# ampelsteuerungeagle.net
KiCad netlist of a schematic drawn in EAGLE
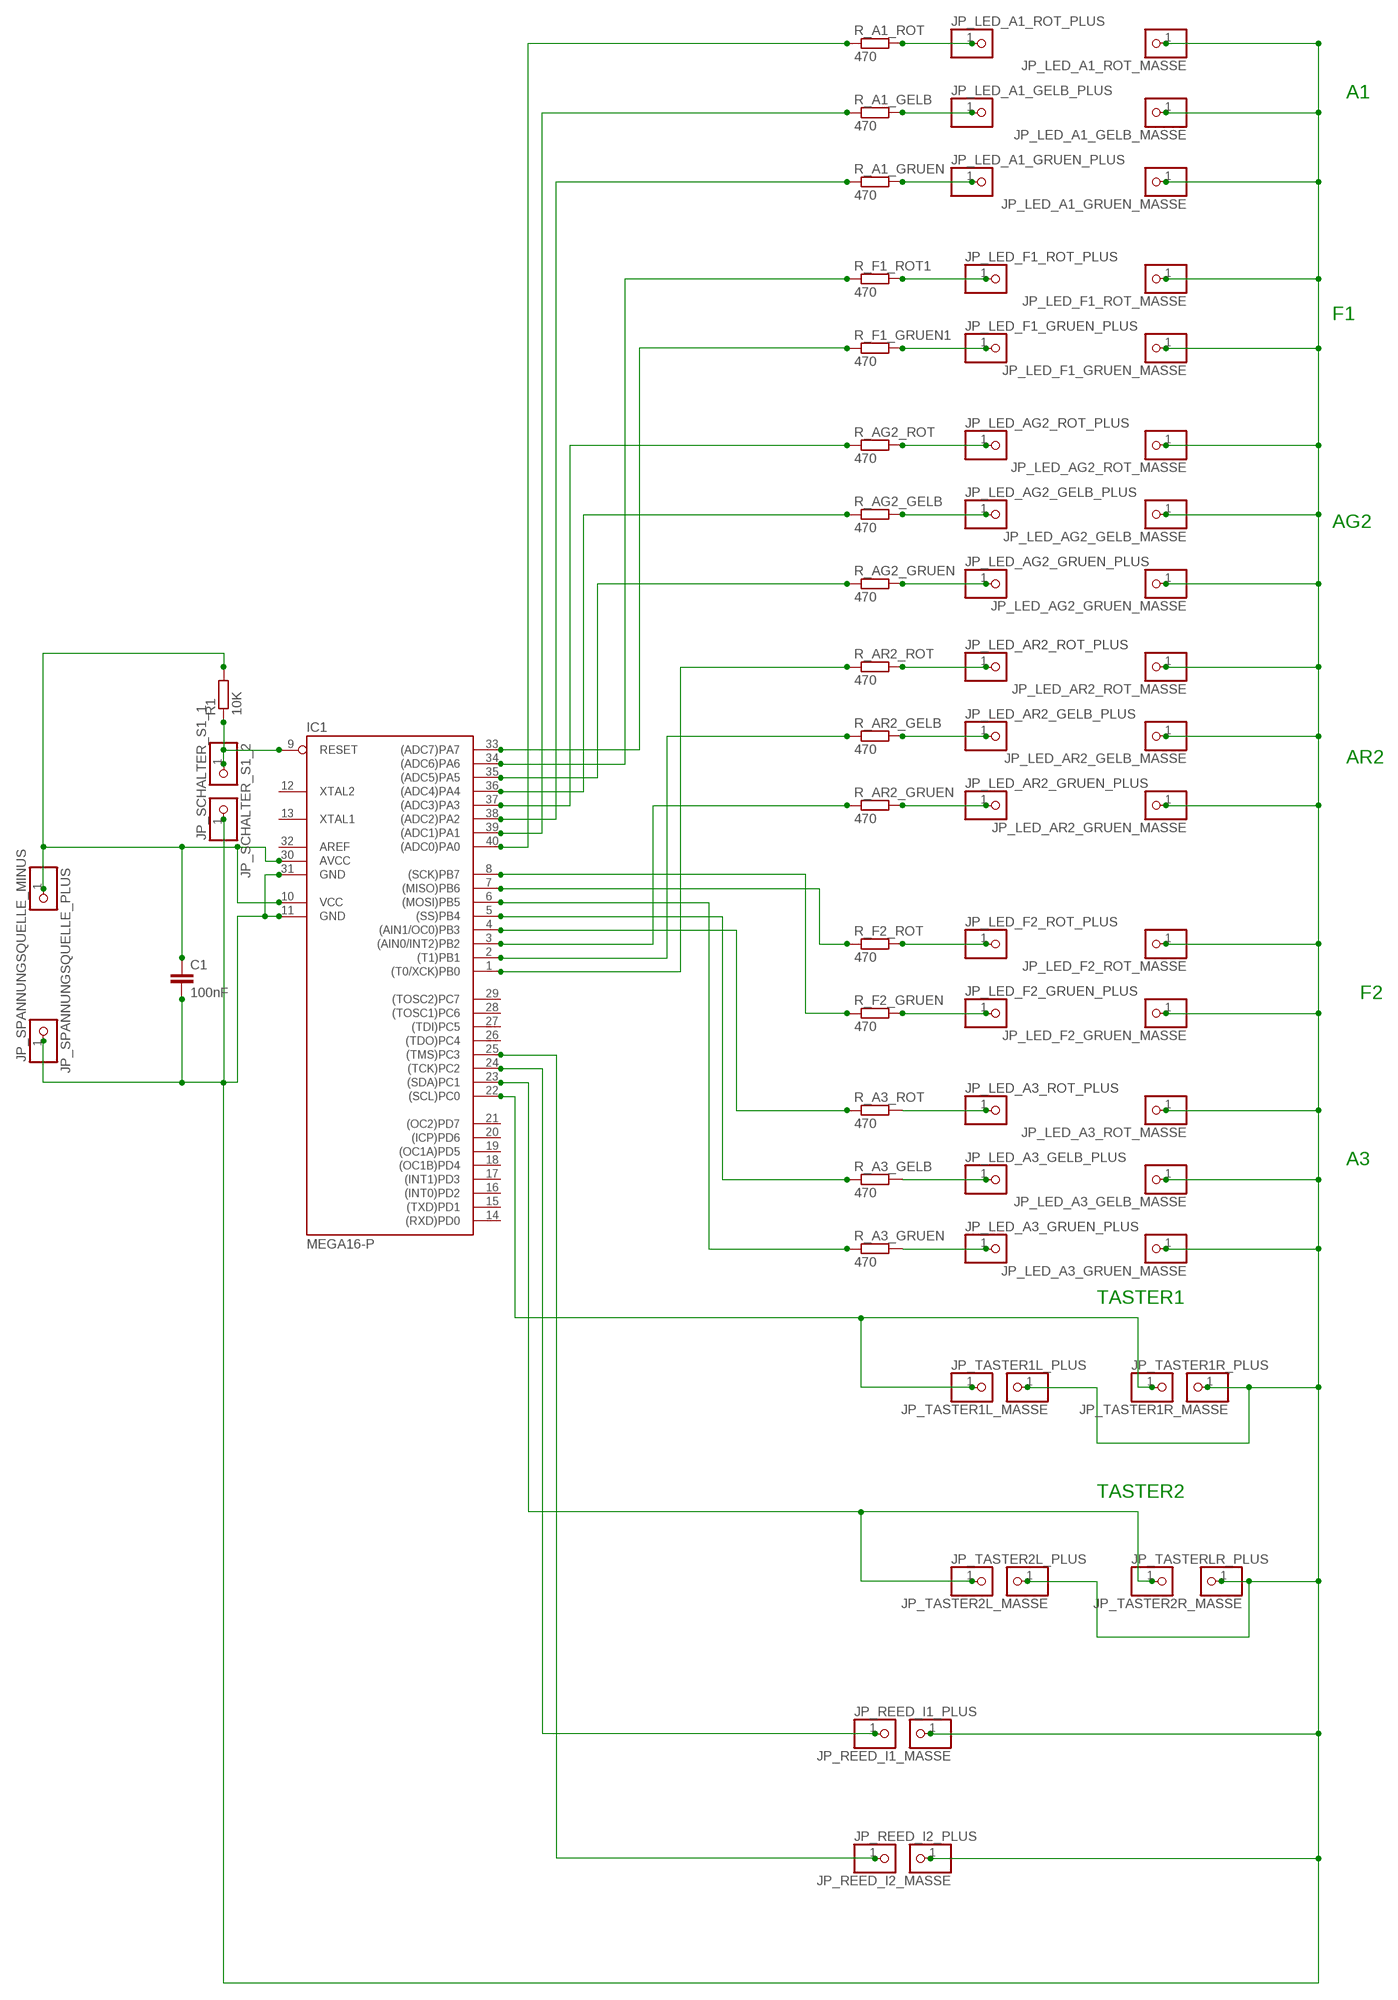
[diagram p0: schematic, sheet 1]

(export (version "E")
  (design (tool "Eeschema 10.0.6"))
  (components
    (comp (ref "C1")
      (value "100nF")
      (footprint "eagle-import:C025-024X044")
      (libsource (lib "eagle-import") (part "C-EU025-024X044"))
    )
    (comp (ref "IC1")
      (value "MEGA16-P")
      (footprint "eagle-import:DIL40")
      (fields (field (name "MPN") "ATMEGA16-16PU"))
      (libsource (lib "eagle-import") (part "MEGA16-P"))
    )
    (comp (ref "JP_LED_A1_GELB_MASSE")
      (value "PINHD-1X1")
      (footprint "eagle-import:1X01")
      (libsource (lib "eagle-import") (part "PINHD-1X1"))
    )
    (comp (ref "JP_LED_A1_GELB_PLUS")
      (value "PINHD-1X1")
      (footprint "eagle-import:1X01")
      (libsource (lib "eagle-import") (part "PINHD-1X1"))
    )
    (comp (ref "JP_LED_A1_GRUEN_MASSE")
      (value "PINHD-1X1")
      (footprint "eagle-import:1X01")
      (libsource (lib "eagle-import") (part "PINHD-1X1"))
    )
    (comp (ref "JP_LED_A1_GRUEN_PLUS")
      (value "PINHD-1X1")
      (footprint "eagle-import:1X01")
      (libsource (lib "eagle-import") (part "PINHD-1X1"))
    )
    (comp (ref "JP_LED_A1_ROT_MASSE")
      (value "PINHD-1X1")
      (footprint "eagle-import:1X01")
      (libsource (lib "eagle-import") (part "PINHD-1X1"))
    )
    (comp (ref "JP_LED_A1_ROT_PLUS")
      (value "PINHD-1X1")
      (footprint "eagle-import:1X01")
      (libsource (lib "eagle-import") (part "PINHD-1X1"))
    )
    (comp (ref "JP_LED_A3_GELB_MASSE")
      (value "PINHD-1X1")
      (footprint "eagle-import:1X01")
      (libsource (lib "eagle-import") (part "PINHD-1X1"))
    )
    (comp (ref "JP_LED_A3_GELB_PLUS")
      (value "PINHD-1X1")
      (footprint "eagle-import:1X01")
      (libsource (lib "eagle-import") (part "PINHD-1X1"))
    )
    (comp (ref "JP_LED_A3_GRUEN_MASSE")
      (value "PINHD-1X1")
      (footprint "eagle-import:1X01")
      (libsource (lib "eagle-import") (part "PINHD-1X1"))
    )
    (comp (ref "JP_LED_A3_GRUEN_PLUS")
      (value "PINHD-1X1")
      (footprint "eagle-import:1X01")
      (libsource (lib "eagle-import") (part "PINHD-1X1"))
    )
    (comp (ref "JP_LED_A3_ROT_MASSE")
      (value "PINHD-1X1")
      (footprint "eagle-import:1X01")
      (libsource (lib "eagle-import") (part "PINHD-1X1"))
    )
    (comp (ref "JP_LED_A3_ROT_PLUS")
      (value "PINHD-1X1")
      (footprint "eagle-import:1X01")
      (libsource (lib "eagle-import") (part "PINHD-1X1"))
    )
    (comp (ref "JP_LED_AG2_GELB_MASSE")
      (value "PINHD-1X1")
      (footprint "eagle-import:1X01")
      (libsource (lib "eagle-import") (part "PINHD-1X1"))
    )
    (comp (ref "JP_LED_AG2_GELB_PLUS")
      (value "PINHD-1X1")
      (footprint "eagle-import:1X01")
      (libsource (lib "eagle-import") (part "PINHD-1X1"))
    )
    (comp (ref "JP_LED_AG2_GRUEN_MASSE")
      (value "PINHD-1X1")
      (footprint "eagle-import:1X01")
      (libsource (lib "eagle-import") (part "PINHD-1X1"))
    )
    (comp (ref "JP_LED_AG2_GRUEN_PLUS")
      (value "PINHD-1X1")
      (footprint "eagle-import:1X01")
      (libsource (lib "eagle-import") (part "PINHD-1X1"))
    )
    (comp (ref "JP_LED_AG2_ROT_MASSE")
      (value "PINHD-1X1")
      (footprint "eagle-import:1X01")
      (libsource (lib "eagle-import") (part "PINHD-1X1"))
    )
    (comp (ref "JP_LED_AG2_ROT_PLUS")
      (value "PINHD-1X1")
      (footprint "eagle-import:1X01")
      (libsource (lib "eagle-import") (part "PINHD-1X1"))
    )
    (comp (ref "JP_LED_AR2_GELB_MASSE")
      (value "PINHD-1X1")
      (footprint "eagle-import:1X01")
      (libsource (lib "eagle-import") (part "PINHD-1X1"))
    )
    (comp (ref "JP_LED_AR2_GELB_PLUS")
      (value "PINHD-1X1")
      (footprint "eagle-import:1X01")
      (libsource (lib "eagle-import") (part "PINHD-1X1"))
    )
    (comp (ref "JP_LED_AR2_GRUEN_MASSE")
      (value "PINHD-1X1")
      (footprint "eagle-import:1X01")
      (libsource (lib "eagle-import") (part "PINHD-1X1"))
    )
    (comp (ref "JP_LED_AR2_GRUEN_PLUS")
      (value "PINHD-1X1")
      (footprint "eagle-import:1X01")
      (libsource (lib "eagle-import") (part "PINHD-1X1"))
    )
    (comp (ref "JP_LED_AR2_ROT_MASSE")
      (value "PINHD-1X1")
      (footprint "eagle-import:1X01")
      (libsource (lib "eagle-import") (part "PINHD-1X1"))
    )
    (comp (ref "JP_LED_AR2_ROT_PLUS")
      (value "PINHD-1X1")
      (footprint "eagle-import:1X01")
      (libsource (lib "eagle-import") (part "PINHD-1X1"))
    )
    (comp (ref "JP_LED_F1_GRUEN_MASSE")
      (value "PINHD-1X1")
      (footprint "eagle-import:1X01")
      (libsource (lib "eagle-import") (part "PINHD-1X1"))
    )
    (comp (ref "JP_LED_F1_GRUEN_PLUS")
      (value "PINHD-1X1")
      (footprint "eagle-import:1X01")
      (libsource (lib "eagle-import") (part "PINHD-1X1"))
    )
    (comp (ref "JP_LED_F1_ROT_MASSE")
      (value "PINHD-1X1")
      (footprint "eagle-import:1X01")
      (libsource (lib "eagle-import") (part "PINHD-1X1"))
    )
    (comp (ref "JP_LED_F1_ROT_PLUS")
      (value "PINHD-1X1")
      (footprint "eagle-import:1X01")
      (libsource (lib "eagle-import") (part "PINHD-1X1"))
    )
    (comp (ref "JP_LED_F2_GRUEN_MASSE")
      (value "PINHD-1X1")
      (footprint "eagle-import:1X01")
      (libsource (lib "eagle-import") (part "PINHD-1X1"))
    )
    (comp (ref "JP_LED_F2_GRUEN_PLUS")
      (value "PINHD-1X1")
      (footprint "eagle-import:1X01")
      (libsource (lib "eagle-import") (part "PINHD-1X1"))
    )
    (comp (ref "JP_LED_F2_ROT_MASSE")
      (value "PINHD-1X1")
      (footprint "eagle-import:1X01")
      (libsource (lib "eagle-import") (part "PINHD-1X1"))
    )
    (comp (ref "JP_LED_F2_ROT_PLUS")
      (value "PINHD-1X1")
      (footprint "eagle-import:1X01")
      (libsource (lib "eagle-import") (part "PINHD-1X1"))
    )
    (comp (ref "JP_REED_I1_MASSE")
      (value "PINHD-1X1")
      (footprint "eagle-import:1X01")
      (libsource (lib "eagle-import") (part "PINHD-1X1"))
    )
    (comp (ref "JP_REED_I1_PLUS")
      (value "PINHD-1X1")
      (footprint "eagle-import:1X01")
      (libsource (lib "eagle-import") (part "PINHD-1X1"))
    )
    (comp (ref "JP_REED_I2_MASSE")
      (value "PINHD-1X1")
      (footprint "eagle-import:1X01")
      (libsource (lib "eagle-import") (part "PINHD-1X1"))
    )
    (comp (ref "JP_REED_I2_PLUS")
      (value "PINHD-1X1")
      (footprint "eagle-import:1X01")
      (libsource (lib "eagle-import") (part "PINHD-1X1"))
    )
    (comp (ref "JP_SCHALTER_S1_1")
      (value "PINHD-1X1")
      (footprint "eagle-import:1X01")
      (libsource (lib "eagle-import") (part "PINHD-1X1"))
    )
    (comp (ref "JP_SCHALTER_S1_2")
      (value "PINHD-1X1")
      (footprint "eagle-import:1X01")
      (libsource (lib "eagle-import") (part "PINHD-1X1"))
    )
    (comp (ref "JP_SPANNUNGSQUELLE_MINUS")
      (value "PINHD-1X1")
      (footprint "eagle-import:1X01")
      (libsource (lib "eagle-import") (part "PINHD-1X1"))
    )
    (comp (ref "JP_SPANNUNGSQUELLE_PLUS")
      (value "PINHD-1X1")
      (footprint "eagle-import:1X01")
      (libsource (lib "eagle-import") (part "PINHD-1X1"))
    )
    (comp (ref "JP_TASTER1L_MASSE")
      (value "PINHD-1X1")
      (footprint "eagle-import:1X01")
      (libsource (lib "eagle-import") (part "PINHD-1X1"))
    )
    (comp (ref "JP_TASTER1L_PLUS")
      (value "PINHD-1X1")
      (footprint "eagle-import:1X01")
      (libsource (lib "eagle-import") (part "PINHD-1X1"))
    )
    (comp (ref "JP_TASTER1R_MASSE")
      (value "PINHD-1X1")
      (footprint "eagle-import:1X01")
      (libsource (lib "eagle-import") (part "PINHD-1X1"))
    )
    (comp (ref "JP_TASTER1R_PLUS")
      (value "PINHD-1X1")
      (footprint "eagle-import:1X01")
      (libsource (lib "eagle-import") (part "PINHD-1X1"))
    )
    (comp (ref "JP_TASTER2L_MASSE")
      (value "PINHD-1X1")
      (footprint "eagle-import:1X01")
      (libsource (lib "eagle-import") (part "PINHD-1X1"))
    )
    (comp (ref "JP_TASTER2L_PLUS")
      (value "PINHD-1X1")
      (footprint "eagle-import:1X01")
      (libsource (lib "eagle-import") (part "PINHD-1X1"))
    )
    (comp (ref "JP_TASTER2R_MASSE")
      (value "PINHD-1X1")
      (footprint "eagle-import:1X01")
      (libsource (lib "eagle-import") (part "PINHD-1X1"))
    )
    (comp (ref "JP_TASTERLR_PLUS")
      (value "PINHD-1X1")
      (footprint "eagle-import:1X01")
      (libsource (lib "eagle-import") (part "PINHD-1X1"))
    )
    (comp (ref "R1")
      (value "10K")
      (footprint "eagle-import:0204V")
      (libsource (lib "eagle-import") (part "R-EU_0204/2V"))
    )
    (comp (ref "R_A1_GELB")
      (value "470")
      (footprint "eagle-import:0204_7")
      (libsource (lib "eagle-import") (part "R-EU_0204/7"))
    )
    (comp (ref "R_A1_GRUEN")
      (value "470")
      (footprint "eagle-import:0204_7")
      (libsource (lib "eagle-import") (part "R-EU_0204/7"))
    )
    (comp (ref "R_A1_ROT")
      (value "470")
      (footprint "eagle-import:0204_7")
      (libsource (lib "eagle-import") (part "R-EU_0204/7"))
    )
    (comp (ref "R_A3_GELB")
      (value "470")
      (footprint "eagle-import:0204_7")
      (libsource (lib "eagle-import") (part "R-EU_0204/7"))
    )
    (comp (ref "R_A3_GRUEN")
      (value "470")
      (footprint "eagle-import:0204_7")
      (libsource (lib "eagle-import") (part "R-EU_0204/7"))
    )
    (comp (ref "R_A3_ROT")
      (value "470")
      (footprint "eagle-import:0204_7")
      (libsource (lib "eagle-import") (part "R-EU_0204/7"))
    )
    (comp (ref "R_AG2_GELB")
      (value "470")
      (footprint "eagle-import:0204_7")
      (libsource (lib "eagle-import") (part "R-EU_0204/7"))
    )
    (comp (ref "R_AG2_GRUEN")
      (value "470")
      (footprint "eagle-import:0204_7")
      (libsource (lib "eagle-import") (part "R-EU_0204/7"))
    )
    (comp (ref "R_AG2_ROT")
      (value "470")
      (footprint "eagle-import:0204_7")
      (libsource (lib "eagle-import") (part "R-EU_0204/7"))
    )
    (comp (ref "R_AR2_GELB")
      (value "470")
      (footprint "eagle-import:0204_7")
      (libsource (lib "eagle-import") (part "R-EU_0204/7"))
    )
    (comp (ref "R_AR2_GRUEN")
      (value "470")
      (footprint "eagle-import:0204_7")
      (libsource (lib "eagle-import") (part "R-EU_0204/7"))
    )
    (comp (ref "R_AR2_ROT")
      (value "470")
      (footprint "eagle-import:0204_7")
      (libsource (lib "eagle-import") (part "R-EU_0204/7"))
    )
    (comp (ref "R_F1_GRUEN1")
      (value "470")
      (footprint "eagle-import:0204_7")
      (libsource (lib "eagle-import") (part "R-EU_0204/7"))
    )
    (comp (ref "R_F1_ROT1")
      (value "470")
      (footprint "eagle-import:0204_7")
      (libsource (lib "eagle-import") (part "R-EU_0204/7"))
    )
    (comp (ref "R_F2_GRUEN")
      (value "470")
      (footprint "eagle-import:0204_7")
      (libsource (lib "eagle-import") (part "R-EU_0204/7"))
    )
    (comp (ref "R_F2_ROT")
      (value "470")
      (footprint "eagle-import:0204_7")
      (libsource (lib "eagle-import") (part "R-EU_0204/7"))
    )
  )
  (nets
    (net (code "1") (name "Net-(C1-Pad2)") (class "Default")
      (node (ref "C1") (pin "2") (pinfunction "2_2") (pintype "passive"))
      (node (ref "IC1") (pin "11") (pinfunction "GND_11") (pintype "power_in"))
      (node (ref "IC1") (pin "31") (pinfunction "GND_31") (pintype "power_in"))
      (node (ref "JP_LED_A1_GELB_MASSE") (pin "1") (pinfunction "1_1") (pintype "passive"))
      (node (ref "JP_LED_A1_GRUEN_MASSE") (pin "1") (pinfunction "1_1") (pintype "passive"))
      (node (ref "JP_LED_A1_ROT_MASSE") (pin "1") (pinfunction "1_1") (pintype "passive"))
      (node (ref "JP_LED_A3_GELB_MASSE") (pin "1") (pinfunction "1_1") (pintype "passive"))
      (node (ref "JP_LED_A3_GRUEN_MASSE") (pin "1") (pinfunction "1_1") (pintype "passive"))
      (node (ref "JP_LED_A3_ROT_MASSE") (pin "1") (pinfunction "1_1") (pintype "passive"))
      (node (ref "JP_LED_AG2_GELB_MASSE") (pin "1") (pinfunction "1_1") (pintype "passive"))
      (node (ref "JP_LED_AG2_GRUEN_MASSE") (pin "1") (pinfunction "1_1") (pintype "passive"))
      (node (ref "JP_LED_AG2_ROT_MASSE") (pin "1") (pinfunction "1_1") (pintype "passive"))
      (node (ref "JP_LED_AR2_GELB_MASSE") (pin "1") (pinfunction "1_1") (pintype "passive"))
      (node (ref "JP_LED_AR2_GRUEN_MASSE") (pin "1") (pinfunction "1_1") (pintype "passive"))
      (node (ref "JP_LED_AR2_ROT_MASSE") (pin "1") (pinfunction "1_1") (pintype "passive"))
      (node (ref "JP_LED_F1_GRUEN_MASSE") (pin "1") (pinfunction "1_1") (pintype "passive"))
      (node (ref "JP_LED_F1_ROT_MASSE") (pin "1") (pinfunction "1_1") (pintype "passive"))
      (node (ref "JP_LED_F2_GRUEN_MASSE") (pin "1") (pinfunction "1_1") (pintype "passive"))
      (node (ref "JP_LED_F2_ROT_MASSE") (pin "1") (pinfunction "1_1") (pintype "passive"))
      (node (ref "JP_REED_I1_MASSE") (pin "1") (pinfunction "1_1") (pintype "passive"))
      (node (ref "JP_REED_I2_MASSE") (pin "1") (pinfunction "1_1") (pintype "passive"))
      (node (ref "JP_SCHALTER_S1_1") (pin "1") (pinfunction "1_1") (pintype "passive"))
      (node (ref "JP_SPANNUNGSQUELLE_MINUS") (pin "1") (pinfunction "1_1") (pintype "passive"))
      (node (ref "JP_TASTER1L_MASSE") (pin "1") (pinfunction "1_1") (pintype "passive"))
      (node (ref "JP_TASTER1R_MASSE") (pin "1") (pinfunction "1_1") (pintype "passive"))
      (node (ref "JP_TASTER2L_MASSE") (pin "1") (pinfunction "1_1") (pintype "passive"))
      (node (ref "JP_TASTER2R_MASSE") (pin "1") (pinfunction "1_1") (pintype "passive"))
    )
    (net (code "2") (name "Net-(IC1-(ADC0)PA0)") (class "Default")
      (node (ref "IC1") (pin "40") (pinfunction "(ADC0)PA0_40") (pintype "bidirectional"))
      (node (ref "R_A1_ROT") (pin "1") (pinfunction "1_1") (pintype "passive"))
    )
    (net (code "3") (name "Net-(IC1-(ADC1)PA1)") (class "Default")
      (node (ref "IC1") (pin "39") (pinfunction "(ADC1)PA1_39") (pintype "bidirectional"))
      (node (ref "R_A1_GELB") (pin "1") (pinfunction "1_1") (pintype "passive"))
    )
    (net (code "4") (name "Net-(IC1-(ADC2)PA2)") (class "Default")
      (node (ref "IC1") (pin "38") (pinfunction "(ADC2)PA2_38") (pintype "bidirectional"))
      (node (ref "R_A1_GRUEN") (pin "1") (pinfunction "1_1") (pintype "passive"))
    )
    (net (code "5") (name "Net-(IC1-(ADC3)PA3)") (class "Default")
      (node (ref "IC1") (pin "37") (pinfunction "(ADC3)PA3_37") (pintype "bidirectional"))
      (node (ref "R_AG2_ROT") (pin "1") (pinfunction "1_1") (pintype "passive"))
    )
    (net (code "6") (name "Net-(IC1-(ADC4)PA4)") (class "Default")
      (node (ref "IC1") (pin "36") (pinfunction "(ADC4)PA4_36") (pintype "bidirectional"))
      (node (ref "R_AG2_GELB") (pin "1") (pinfunction "1_1") (pintype "passive"))
    )
    (net (code "7") (name "Net-(IC1-(ADC5)PA5)") (class "Default")
      (node (ref "IC1") (pin "35") (pinfunction "(ADC5)PA5_35") (pintype "bidirectional"))
      (node (ref "R_AG2_GRUEN") (pin "1") (pinfunction "1_1") (pintype "passive"))
    )
    (net (code "8") (name "Net-(IC1-(ADC6)PA6)") (class "Default")
      (node (ref "IC1") (pin "34") (pinfunction "(ADC6)PA6_34") (pintype "bidirectional"))
      (node (ref "R_F1_ROT1") (pin "1") (pinfunction "1_1") (pintype "passive"))
    )
    (net (code "9") (name "Net-(IC1-(ADC7)PA7)") (class "Default")
      (node (ref "IC1") (pin "33") (pinfunction "(ADC7)PA7_33") (pintype "bidirectional"))
      (node (ref "R_F1_GRUEN1") (pin "1") (pinfunction "1_1") (pintype "passive"))
    )
    (net (code "10") (name "Net-(IC1-(AIN0{slash}INT2)PB2)") (class "Default")
      (node (ref "IC1") (pin "3") (pinfunction "(AIN0/INT2)PB2_3") (pintype "bidirectional"))
      (node (ref "R_AR2_GRUEN") (pin "1") (pinfunction "1_1") (pintype "passive"))
    )
    (net (code "11") (name "Net-(IC1-(AIN1{slash}OC0)PB3)") (class "Default")
      (node (ref "IC1") (pin "4") (pinfunction "(AIN1/OC0)PB3_4") (pintype "bidirectional"))
      (node (ref "R_A3_ROT") (pin "1") (pinfunction "1_1") (pintype "passive"))
    )
    (net (code "12") (name "Net-(IC1-(MISO)PB6)") (class "Default")
      (node (ref "IC1") (pin "7") (pinfunction "(MISO)PB6_7") (pintype "bidirectional"))
      (node (ref "R_F2_ROT") (pin "1") (pinfunction "1_1") (pintype "passive"))
    )
    (net (code "13") (name "Net-(IC1-(MOSI)PB5)") (class "Default")
      (node (ref "IC1") (pin "6") (pinfunction "(MOSI)PB5_6") (pintype "bidirectional"))
      (node (ref "R_A3_GRUEN") (pin "1") (pinfunction "1_1") (pintype "passive"))
    )
    (net (code "14") (name "Net-(IC1-(SCK)PB7)") (class "Default")
      (node (ref "IC1") (pin "8") (pinfunction "(SCK)PB7_8") (pintype "bidirectional"))
      (node (ref "R_F2_GRUEN") (pin "1") (pinfunction "1_1") (pintype "passive"))
    )
    (net (code "15") (name "Net-(IC1-(SCL)PC0)") (class "Default")
      (node (ref "IC1") (pin "22") (pinfunction "(SCL)PC0_22") (pintype "bidirectional"))
      (node (ref "JP_TASTER1L_PLUS") (pin "1") (pinfunction "1_1") (pintype "passive"))
      (node (ref "JP_TASTER1R_PLUS") (pin "1") (pinfunction "1_1") (pintype "passive"))
    )
    (net (code "16") (name "Net-(IC1-(SDA)PC1)") (class "Default")
      (node (ref "IC1") (pin "23") (pinfunction "(SDA)PC1_23") (pintype "bidirectional"))
      (node (ref "JP_TASTER2L_PLUS") (pin "1") (pinfunction "1_1") (pintype "passive"))
      (node (ref "JP_TASTERLR_PLUS") (pin "1") (pinfunction "1_1") (pintype "passive"))
    )
    (net (code "17") (name "Net-(IC1-(SS)PB4)") (class "Default")
      (node (ref "IC1") (pin "5") (pinfunction "(SS)PB4_5") (pintype "bidirectional"))
      (node (ref "R_A3_GELB") (pin "1") (pinfunction "1_1") (pintype "passive"))
    )
    (net (code "18") (name "Net-(IC1-(T0{slash}XCK)PB0)") (class "Default")
      (node (ref "IC1") (pin "1") (pinfunction "(T0/XCK)PB0_1") (pintype "bidirectional"))
      (node (ref "R_AR2_ROT") (pin "1") (pinfunction "1_1") (pintype "passive"))
    )
    (net (code "19") (name "Net-(IC1-(T1)PB1)") (class "Default")
      (node (ref "IC1") (pin "2") (pinfunction "(T1)PB1_2") (pintype "bidirectional"))
      (node (ref "R_AR2_GELB") (pin "1") (pinfunction "1_1") (pintype "passive"))
    )
    (net (code "20") (name "Net-(IC1-(TCK)PC2)") (class "Default")
      (node (ref "IC1") (pin "24") (pinfunction "(TCK)PC2_24") (pintype "bidirectional"))
      (node (ref "JP_REED_I1_PLUS") (pin "1") (pinfunction "1_1") (pintype "passive"))
    )
    (net (code "21") (name "Net-(IC1-(TMS)PC3)") (class "Default")
      (node (ref "IC1") (pin "25") (pinfunction "(TMS)PC3_25") (pintype "bidirectional"))
      (node (ref "JP_REED_I2_PLUS") (pin "1") (pinfunction "1_1") (pintype "passive"))
    )
    (net (code "22") (name "Net-(IC1-AVCC)") (class "Default")
      (node (ref "C1") (pin "1") (pinfunction "1_1") (pintype "passive"))
      (node (ref "IC1") (pin "10") (pinfunction "VCC_10") (pintype "power_in"))
      (node (ref "IC1") (pin "30") (pinfunction "AVCC_30") (pintype "power_in"))
      (node (ref "JP_SPANNUNGSQUELLE_PLUS") (pin "1") (pinfunction "1_1") (pintype "passive"))
      (node (ref "R1") (pin "2") (pinfunction "2_2") (pintype "passive"))
    )
    (net (code "23") (name "Net-(IC1-RESET)") (class "Default")
      (node (ref "IC1") (pin "9") (pinfunction "RESET_9") (pintype "input"))
      (node (ref "JP_SCHALTER_S1_2") (pin "1") (pinfunction "1_1") (pintype "passive"))
      (node (ref "R1") (pin "1") (pinfunction "1_1") (pintype "passive"))
    )
    (net (code "24") (name "Net-(JP_LED_A1_GELB_PLUS-Pad1)") (class "Default")
      (node (ref "JP_LED_A1_GELB_PLUS") (pin "1") (pinfunction "1_1") (pintype "passive"))
      (node (ref "R_A1_GELB") (pin "2") (pinfunction "2_2") (pintype "passive"))
    )
    (net (code "25") (name "Net-(JP_LED_A1_GRUEN_PLUS-Pad1)") (class "Default")
      (node (ref "JP_LED_A1_GRUEN_PLUS") (pin "1") (pinfunction "1_1") (pintype "passive"))
      (node (ref "R_A1_GRUEN") (pin "2") (pinfunction "2_2") (pintype "passive"))
    )
    (net (code "26") (name "Net-(JP_LED_A1_ROT_PLUS-Pad1)") (class "Default")
      (node (ref "JP_LED_A1_ROT_PLUS") (pin "1") (pinfunction "1_1") (pintype "passive"))
      (node (ref "R_A1_ROT") (pin "2") (pinfunction "2_2") (pintype "passive"))
    )
    (net (code "27") (name "Net-(JP_LED_A3_GELB_PLUS-Pad1)") (class "Default")
      (node (ref "JP_LED_A3_GELB_PLUS") (pin "1") (pinfunction "1_1") (pintype "passive"))
      (node (ref "R_A3_GELB") (pin "2") (pinfunction "2_2") (pintype "passive"))
    )
    (net (code "28") (name "Net-(JP_LED_A3_GRUEN_PLUS-Pad1)") (class "Default")
      (node (ref "JP_LED_A3_GRUEN_PLUS") (pin "1") (pinfunction "1_1") (pintype "passive"))
      (node (ref "R_A3_GRUEN") (pin "2") (pinfunction "2_2") (pintype "passive"))
    )
    (net (code "29") (name "Net-(JP_LED_A3_ROT_PLUS-Pad1)") (class "Default")
      (node (ref "JP_LED_A3_ROT_PLUS") (pin "1") (pinfunction "1_1") (pintype "passive"))
      (node (ref "R_A3_ROT") (pin "2") (pinfunction "2_2") (pintype "passive"))
    )
    (net (code "30") (name "Net-(JP_LED_AG2_GELB_PLUS-Pad1)") (class "Default")
      (node (ref "JP_LED_AG2_GELB_PLUS") (pin "1") (pinfunction "1_1") (pintype "passive"))
      (node (ref "R_AG2_GELB") (pin "2") (pinfunction "2_2") (pintype "passive"))
    )
    (net (code "31") (name "Net-(JP_LED_AG2_GRUEN_PLUS-Pad1)") (class "Default")
      (node (ref "JP_LED_AG2_GRUEN_PLUS") (pin "1") (pinfunction "1_1") (pintype "passive"))
      (node (ref "R_AG2_GRUEN") (pin "2") (pinfunction "2_2") (pintype "passive"))
    )
    (net (code "32") (name "Net-(JP_LED_AG2_ROT_PLUS-Pad1)") (class "Default")
      (node (ref "JP_LED_AG2_ROT_PLUS") (pin "1") (pinfunction "1_1") (pintype "passive"))
      (node (ref "R_AG2_ROT") (pin "2") (pinfunction "2_2") (pintype "passive"))
    )
    (net (code "33") (name "Net-(JP_LED_AR2_GELB_PLUS-Pad1)") (class "Default")
      (node (ref "JP_LED_AR2_GELB_PLUS") (pin "1") (pinfunction "1_1") (pintype "passive"))
      (node (ref "R_AR2_GELB") (pin "2") (pinfunction "2_2") (pintype "passive"))
    )
    (net (code "34") (name "Net-(JP_LED_AR2_GRUEN_PLUS-Pad1)") (class "Default")
      (node (ref "JP_LED_AR2_GRUEN_PLUS") (pin "1") (pinfunction "1_1") (pintype "passive"))
      (node (ref "R_AR2_GRUEN") (pin "2") (pinfunction "2_2") (pintype "passive"))
    )
    (net (code "35") (name "Net-(JP_LED_AR2_ROT_PLUS-Pad1)") (class "Default")
      (node (ref "JP_LED_AR2_ROT_PLUS") (pin "1") (pinfunction "1_1") (pintype "passive"))
      (node (ref "R_AR2_ROT") (pin "2") (pinfunction "2_2") (pintype "passive"))
    )
    (net (code "36") (name "Net-(JP_LED_F1_GRUEN_PLUS-Pad1)") (class "Default")
      (node (ref "JP_LED_F1_GRUEN_PLUS") (pin "1") (pinfunction "1_1") (pintype "passive"))
      (node (ref "R_F1_GRUEN1") (pin "2") (pinfunction "2_2") (pintype "passive"))
    )
    (net (code "37") (name "Net-(JP_LED_F1_ROT_PLUS-Pad1)") (class "Default")
      (node (ref "JP_LED_F1_ROT_PLUS") (pin "1") (pinfunction "1_1") (pintype "passive"))
      (node (ref "R_F1_ROT1") (pin "2") (pinfunction "2_2") (pintype "passive"))
    )
    (net (code "38") (name "Net-(JP_LED_F2_GRUEN_PLUS-Pad1)") (class "Default")
      (node (ref "JP_LED_F2_GRUEN_PLUS") (pin "1") (pinfunction "1_1") (pintype "passive"))
      (node (ref "R_F2_GRUEN") (pin "2") (pinfunction "2_2") (pintype "passive"))
    )
    (net (code "39") (name "Net-(JP_LED_F2_ROT_PLUS-Pad1)") (class "Default")
      (node (ref "JP_LED_F2_ROT_PLUS") (pin "1") (pinfunction "1_1") (pintype "passive"))
      (node (ref "R_F2_ROT") (pin "2") (pinfunction "2_2") (pintype "passive"))
    )
    (net (code "40") (name "unconnected-(IC1-(ICP)PD6-Pad20)") (class "Default")
      (node (ref "IC1") (pin "20") (pinfunction "(ICP)PD6_20") (pintype "bidirectional"))
    )
    (net (code "41") (name "unconnected-(IC1-(INT0)PD2-Pad16)") (class "Default")
      (node (ref "IC1") (pin "16") (pinfunction "(INT0)PD2_16") (pintype "bidirectional"))
    )
    (net (code "42") (name "unconnected-(IC1-(INT1)PD3-Pad17)") (class "Default")
      (node (ref "IC1") (pin "17") (pinfunction "(INT1)PD3_17") (pintype "bidirectional"))
    )
    (net (code "43") (name "unconnected-(IC1-(OC1A)PD5-Pad19)") (class "Default")
      (node (ref "IC1") (pin "19") (pinfunction "(OC1A)PD5_19") (pintype "bidirectional"))
    )
    (net (code "44") (name "unconnected-(IC1-(OC1B)PD4-Pad18)") (class "Default")
      (node (ref "IC1") (pin "18") (pinfunction "(OC1B)PD4_18") (pintype "bidirectional"))
    )
    (net (code "45") (name "unconnected-(IC1-(OC2)PD7-Pad21)") (class "Default")
      (node (ref "IC1") (pin "21") (pinfunction "(OC2)PD7_21") (pintype "bidirectional"))
    )
    (net (code "46") (name "unconnected-(IC1-(RXD)PD0-Pad14)") (class "Default")
      (node (ref "IC1") (pin "14") (pinfunction "(RXD)PD0_14") (pintype "bidirectional"))
    )
    (net (code "47") (name "unconnected-(IC1-(TDI)PC5-Pad27)") (class "Default")
      (node (ref "IC1") (pin "27") (pinfunction "(TDI)PC5_27") (pintype "bidirectional"))
    )
    (net (code "48") (name "unconnected-(IC1-(TDO)PC4-Pad26)") (class "Default")
      (node (ref "IC1") (pin "26") (pinfunction "(TDO)PC4_26") (pintype "bidirectional"))
    )
    (net (code "49") (name "unconnected-(IC1-(TOSC1)PC6-Pad28)") (class "Default")
      (node (ref "IC1") (pin "28") (pinfunction "(TOSC1)PC6_28") (pintype "bidirectional"))
    )
    (net (code "50") (name "unconnected-(IC1-(TOSC2)PC7-Pad29)") (class "Default")
      (node (ref "IC1") (pin "29") (pinfunction "(TOSC2)PC7_29") (pintype "bidirectional"))
    )
    (net (code "51") (name "unconnected-(IC1-(TXD)PD1-Pad15)") (class "Default")
      (node (ref "IC1") (pin "15") (pinfunction "(TXD)PD1_15") (pintype "bidirectional"))
    )
    (net (code "52") (name "unconnected-(IC1-AREF-Pad32)") (class "Default")
      (node (ref "IC1") (pin "32") (pinfunction "AREF_32") (pintype "passive"))
    )
    (net (code "53") (name "unconnected-(IC1-XTAL1-Pad13)") (class "Default")
      (node (ref "IC1") (pin "13") (pinfunction "XTAL1_13") (pintype "bidirectional"))
    )
    (net (code "54") (name "unconnected-(IC1-XTAL2-Pad12)") (class "Default")
      (node (ref "IC1") (pin "12") (pinfunction "XTAL2_12") (pintype "bidirectional"))
    )
  )
)
